# Z80-Clock-And-Reset-1-2.net
KiCad netlist of a schematic drawn in EAGLE
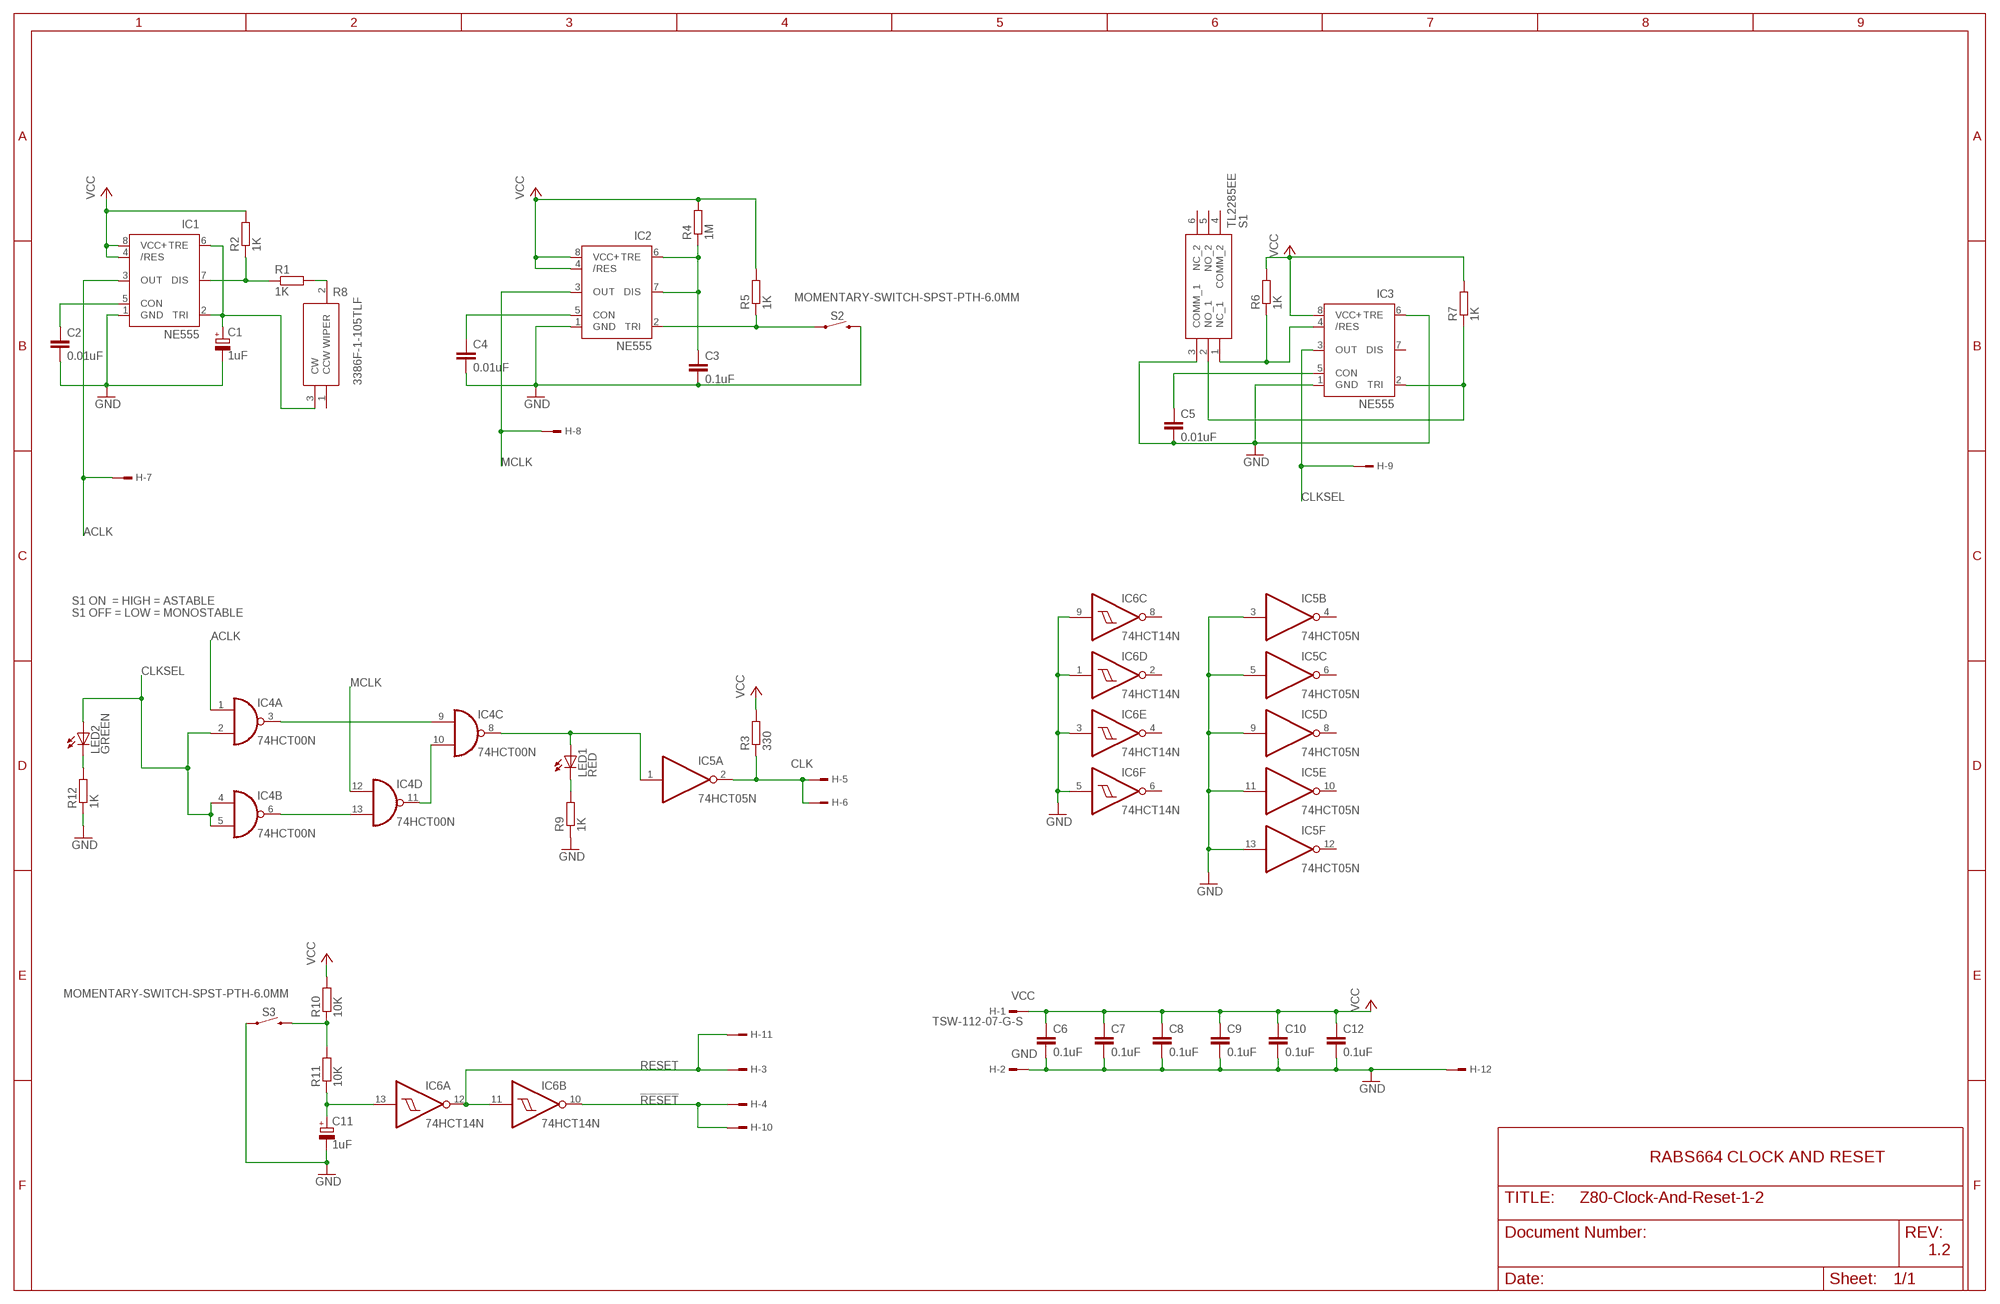
[diagram p0: schematic, sheet 1]

(export (version "E")
  (design (tool "Eeschema 10.0.6"))
  (components
    (comp (ref "C1")
      (value "1uF")
      (footprint "eagle-import:E2,5-6E")
      (libsource (lib "eagle-import") (part "CPOL-EUE2,5-6E"))
    )
    (comp (ref "C2")
      (value "0.01uF")
      (footprint "eagle-import:C050-025X075")
      (libsource (lib "eagle-import") (part "C-EU050-025X075"))
    )
    (comp (ref "C3")
      (value "0.1uF")
      (footprint "eagle-import:C050-025X075")
      (libsource (lib "eagle-import") (part "C-EU050-025X075"))
    )
    (comp (ref "C4")
      (value "0.01uF")
      (footprint "eagle-import:C050-025X075")
      (libsource (lib "eagle-import") (part "C-EU050-025X075"))
    )
    (comp (ref "C5")
      (value "0.01uF")
      (footprint "eagle-import:C050-025X075")
      (libsource (lib "eagle-import") (part "C-EU050-025X075"))
    )
    (comp (ref "C6")
      (value "0.1uF")
      (footprint "eagle-import:C050-025X075")
      (libsource (lib "eagle-import") (part "C-EU050-025X075"))
    )
    (comp (ref "C7")
      (value "0.1uF")
      (footprint "eagle-import:C050-025X075")
      (libsource (lib "eagle-import") (part "C-EU050-025X075"))
    )
    (comp (ref "C8")
      (value "0.1uF")
      (footprint "eagle-import:C050-025X075")
      (libsource (lib "eagle-import") (part "C-EU050-025X075"))
    )
    (comp (ref "C9")
      (value "0.1uF")
      (footprint "eagle-import:C050-025X075")
      (libsource (lib "eagle-import") (part "C-EU050-025X075"))
    )
    (comp (ref "C10")
      (value "0.1uF")
      (footprint "eagle-import:C050-025X075")
      (libsource (lib "eagle-import") (part "C-EU050-025X075"))
    )
    (comp (ref "C11")
      (value "1uF")
      (footprint "eagle-import:E2,5-6E")
      (libsource (lib "eagle-import") (part "CPOL-EUE2,5-6E"))
    )
    (comp (ref "C12")
      (value "0.1uF")
      (footprint "eagle-import:C050-025X075")
      (libsource (lib "eagle-import") (part "C-EU050-025X075"))
    )
    (comp (ref "H")
      (value "TSW-112-07-G-S")
      (footprint "eagle-import:TSW-112-XX-G-S")
      (fields (field (name "MF") "Samtec Inc."))
      (libsource (lib "eagle-import") (part "TSW-112--G-S07"))
    )
    (comp (ref "IC1")
      (value "NE555")
      (footprint "eagle-import:DIL-08")
      (fields (field (name "MF") "Arrow Electronics") (field (name "MPN") "NE555N"))
      (libsource (lib "eagle-import") (part "NE555"))
    )
    (comp (ref "IC2")
      (value "NE555")
      (footprint "eagle-import:DIL-08")
      (fields (field (name "MF") "Arrow Electronics") (field (name "MPN") "NE555N"))
      (libsource (lib "eagle-import") (part "NE555"))
    )
    (comp (ref "IC3")
      (value "NE555")
      (footprint "eagle-import:DIL-08")
      (fields (field (name "MF") "Arrow Electronics") (field (name "MPN") "NE555N"))
      (libsource (lib "eagle-import") (part "NE555"))
    )
    (comp (ref "IC4")
      (value "74HCT00N")
      (footprint "eagle-import:DIL14")
      (libsource (lib "eagle-import") (part "7400NHCT"))
    )
    (comp (ref "IC5")
      (value "74HCT05N")
      (footprint "eagle-import:DIL14")
      (libsource (lib "eagle-import") (part "7405NHCT"))
    )
    (comp (ref "IC6")
      (value "74HCT14N")
      (footprint "eagle-import:DIL14")
      (libsource (lib "eagle-import") (part "7414NHCT"))
    )
    (comp (ref "LED1")
      (value "RED")
      (footprint "eagle-import:LED3MM")
      (libsource (lib "eagle-import") (part "LED3MM"))
    )
    (comp (ref "LED2")
      (value "GREEN")
      (footprint "eagle-import:LED3MM")
      (libsource (lib "eagle-import") (part "LED3MM"))
    )
    (comp (ref "R1")
      (value "1K")
      (footprint "eagle-import:0207_10")
      (libsource (lib "eagle-import") (part "R-EU_0207/10"))
    )
    (comp (ref "R2")
      (value "1K")
      (footprint "eagle-import:0207_10")
      (libsource (lib "eagle-import") (part "R-EU_0207/10"))
    )
    (comp (ref "R3")
      (value "330")
      (footprint "eagle-import:0207_10")
      (libsource (lib "eagle-import") (part "R-EU_0207/10"))
    )
    (comp (ref "R4")
      (value "1M")
      (footprint "eagle-import:0207_10")
      (libsource (lib "eagle-import") (part "R-EU_0207/10"))
    )
    (comp (ref "R5")
      (value "1K")
      (footprint "eagle-import:0207_10")
      (libsource (lib "eagle-import") (part "R-EU_0207/10"))
    )
    (comp (ref "R6")
      (value "1K")
      (footprint "eagle-import:0207_10")
      (libsource (lib "eagle-import") (part "R-EU_0207/10"))
    )
    (comp (ref "R7")
      (value "1K")
      (footprint "eagle-import:0207_10")
      (libsource (lib "eagle-import") (part "R-EU_0207/10"))
    )
    (comp (ref "R8")
      (value "3386F-1-103TLF")
      (footprint "eagle-import:3386F1103TLF")
      (fields (field (name "MOUSER_PART_NUMBER") "652-3386F-1-103TLF"))
      (libsource (lib "eagle-import") (part "3386F-1-103TLF"))
    )
    (comp (ref "R9")
      (value "1K")
      (footprint "eagle-import:0207_10")
      (libsource (lib "eagle-import") (part "R-EU_0207/10"))
    )
    (comp (ref "R10")
      (value "10K")
      (footprint "eagle-import:0207_10")
      (libsource (lib "eagle-import") (part "R-EU_0207/10"))
    )
    (comp (ref "R11")
      (value "10K")
      (footprint "eagle-import:0207_10")
      (libsource (lib "eagle-import") (part "R-EU_0207/10"))
    )
    (comp (ref "R12")
      (value "1K")
      (footprint "eagle-import:0207_10")
      (libsource (lib "eagle-import") (part "R-EU_0207/10"))
    )
    (comp (ref "S1")
      (value "TL2285EE")
      (footprint "eagle-import:TL2285EE")
      (fields (field (name "MOUSER_PART_NUMBER") "612-TL2285EE"))
      (libsource (lib "eagle-import") (part "TL2285EE"))
    )
    (comp (ref "S2")
      (value "MOMENTARY-SWITCH-SPST-PTH-6.0MM")
      (footprint "eagle-import:TACTILE_SWITCH_PTH_6.0MM")
      (libsource (lib "eagle-import") (part "MOMENTARY-SWITCH-SPST-PTH-6.0MM"))
    )
    (comp (ref "S3")
      (value "MOMENTARY-SWITCH-SPST-PTH-6.0MM")
      (footprint "eagle-import:TACTILE_SWITCH_PTH_6.0MM")
      (libsource (lib "eagle-import") (part "MOMENTARY-SWITCH-SPST-PTH-6.0MM"))
    )
  )
  (nets
    (net (code "1") (name "/ACLK") (class "Default")
      (node (ref "H") (pin "7") (pinfunction "1_7") (pintype "passive"))
      (node (ref "IC1") (pin "3") (pinfunction "OUT_3") (pintype "output"))
      (node (ref "IC4") (pin "1") (pinfunction "I0_1") (pintype "input"))
    )
    (net (code "2") (name "/CLK") (class "Default")
      (node (ref "H") (pin "5") (pinfunction "1_5") (pintype "passive"))
      (node (ref "H") (pin "6") (pinfunction "1_6") (pintype "passive"))
      (node (ref "IC5") (pin "2") (pinfunction "O_2") (pintype "open_collector"))
      (node (ref "R3") (pin "1") (pinfunction "1_1") (pintype "passive"))
    )
    (net (code "3") (name "/CLKSEL") (class "Default")
      (node (ref "H") (pin "9") (pinfunction "1_9") (pintype "passive"))
      (node (ref "IC3") (pin "3") (pinfunction "OUT_3") (pintype "output"))
      (node (ref "IC4") (pin "2") (pinfunction "I1_2") (pintype "input"))
      (node (ref "IC4") (pin "4") (pinfunction "I0_4") (pintype "input"))
      (node (ref "IC4") (pin "5") (pinfunction "I1_5") (pintype "input"))
      (node (ref "LED2") (pin "A") (pinfunction "A_A") (pintype "passive"))
    )
    (net (code "4") (name "/MCLK") (class "Default")
      (node (ref "H") (pin "8") (pinfunction "1_8") (pintype "passive"))
      (node (ref "IC2") (pin "3") (pinfunction "OUT_3") (pintype "output"))
      (node (ref "IC4") (pin "12") (pinfunction "I0_12") (pintype "input"))
    )
    (net (code "5") (name "/RESET") (class "Default")
      (node (ref "H") (pin "11") (pinfunction "1_11") (pintype "passive"))
      (node (ref "H") (pin "3") (pinfunction "1_3") (pintype "passive"))
      (node (ref "IC6") (pin "11") (pinfunction "I_11") (pintype "input"))
      (node (ref "IC6") (pin "12") (pinfunction "O_12") (pintype "output"))
    )
    (net (code "6") (name "/~{RESET}") (class "Default")
      (node (ref "H") (pin "10") (pinfunction "1_10") (pintype "passive"))
      (node (ref "H") (pin "4") (pinfunction "1_4") (pintype "passive"))
      (node (ref "IC6") (pin "10") (pinfunction "O_10") (pintype "output"))
    )
    (net (code "7") (name "GND") (class "Default")
      (node (ref "C1") (pin "-") (pinfunction "-_-") (pintype "passive"))
      (node (ref "C10") (pin "2") (pinfunction "2_2") (pintype "passive"))
      (node (ref "C11") (pin "-") (pinfunction "-_-") (pintype "passive"))
      (node (ref "C12") (pin "2") (pinfunction "2_2") (pintype "passive"))
      (node (ref "C2") (pin "2") (pinfunction "2_2") (pintype "passive"))
      (node (ref "C3") (pin "2") (pinfunction "2_2") (pintype "passive"))
      (node (ref "C4") (pin "2") (pinfunction "2_2") (pintype "passive"))
      (node (ref "C5") (pin "2") (pinfunction "2_2") (pintype "passive"))
      (node (ref "C6") (pin "2") (pinfunction "2_2") (pintype "passive"))
      (node (ref "C7") (pin "2") (pinfunction "2_2") (pintype "passive"))
      (node (ref "C8") (pin "2") (pinfunction "2_2") (pintype "passive"))
      (node (ref "C9") (pin "2") (pinfunction "2_2") (pintype "passive"))
      (node (ref "H") (pin "12") (pinfunction "1_12") (pintype "passive"))
      (node (ref "H") (pin "2") (pinfunction "1_2") (pintype "passive"))
      (node (ref "IC1") (pin "1") (pinfunction "GND_1") (pintype "power_in"))
      (node (ref "IC2") (pin "1") (pinfunction "GND_1") (pintype "power_in"))
      (node (ref "IC3") (pin "1") (pinfunction "GND_1") (pintype "power_in"))
      (node (ref "IC3") (pin "6") (pinfunction "TRE_6") (pintype "input"))
      (node (ref "IC5") (pin "11") (pinfunction "I_11") (pintype "input"))
      (node (ref "IC5") (pin "13") (pinfunction "I_13") (pintype "input"))
      (node (ref "IC5") (pin "3") (pinfunction "I_3") (pintype "input"))
      (node (ref "IC5") (pin "5") (pinfunction "I_5") (pintype "input"))
      (node (ref "IC5") (pin "9") (pinfunction "I_9") (pintype "input"))
      (node (ref "IC6") (pin "1") (pinfunction "I_1") (pintype "input"))
      (node (ref "IC6") (pin "3") (pinfunction "I_3") (pintype "input"))
      (node (ref "IC6") (pin "5") (pinfunction "I_5") (pintype "input"))
      (node (ref "IC6") (pin "9") (pinfunction "I_9") (pintype "input"))
      (node (ref "R12") (pin "1") (pinfunction "1_1") (pintype "passive"))
      (node (ref "R9") (pin "1") (pinfunction "1_1") (pintype "passive"))
      (node (ref "S1") (pin "3") (pinfunction "COMM_1_3") (pintype "bidirectional"))
      (node (ref "S2") (pin "3") (pinfunction "2_3") (pintype "passive"))
      (node (ref "S3") (pin "1") (pinfunction "1_1") (pintype "passive"))
    )
    (net (code "8") (name "Net-(IC1-CON)") (class "Default")
      (node (ref "C2") (pin "1") (pinfunction "1_1") (pintype "passive"))
      (node (ref "IC1") (pin "5") (pinfunction "CON_5") (pintype "input"))
    )
    (net (code "9") (name "Net-(IC1-DIS)") (class "Default")
      (node (ref "IC1") (pin "7") (pinfunction "DIS_7") (pintype "input"))
      (node (ref "R1") (pin "1") (pinfunction "1_1") (pintype "passive"))
      (node (ref "R2") (pin "1") (pinfunction "1_1") (pintype "passive"))
    )
    (net (code "10") (name "Net-(IC1-TRE)") (class "Default")
      (node (ref "C1") (pin "+") (pinfunction "+_+") (pintype "passive"))
      (node (ref "IC1") (pin "2") (pinfunction "TRI_2") (pintype "input"))
      (node (ref "IC1") (pin "6") (pinfunction "TRE_6") (pintype "input"))
      (node (ref "R8") (pin "3") (pinfunction "CW_3") (pintype "bidirectional"))
    )
    (net (code "11") (name "Net-(IC2-CON)") (class "Default")
      (node (ref "C4") (pin "1") (pinfunction "1_1") (pintype "passive"))
      (node (ref "IC2") (pin "5") (pinfunction "CON_5") (pintype "input"))
    )
    (net (code "12") (name "Net-(IC2-DIS)") (class "Default")
      (node (ref "C3") (pin "1") (pinfunction "1_1") (pintype "passive"))
      (node (ref "IC2") (pin "6") (pinfunction "TRE_6") (pintype "input"))
      (node (ref "IC2") (pin "7") (pinfunction "DIS_7") (pintype "input"))
      (node (ref "R4") (pin "1") (pinfunction "1_1") (pintype "passive"))
    )
    (net (code "13") (name "Net-(IC2-TRI)") (class "Default")
      (node (ref "IC2") (pin "2") (pinfunction "TRI_2") (pintype "input"))
      (node (ref "R5") (pin "1") (pinfunction "1_1") (pintype "passive"))
      (node (ref "S2") (pin "1") (pinfunction "1_1") (pintype "passive"))
    )
    (net (code "14") (name "Net-(IC3-CON)") (class "Default")
      (node (ref "C5") (pin "1") (pinfunction "1_1") (pintype "passive"))
      (node (ref "IC3") (pin "5") (pinfunction "CON_5") (pintype "input"))
    )
    (net (code "15") (name "Net-(IC3-TRI)") (class "Default")
      (node (ref "IC3") (pin "2") (pinfunction "TRI_2") (pintype "input"))
      (node (ref "R7") (pin "1") (pinfunction "1_1") (pintype "passive"))
      (node (ref "S1") (pin "2") (pinfunction "NO_1_2") (pintype "bidirectional"))
    )
    (net (code "16") (name "Net-(IC3-{slash}RES)") (class "Default")
      (node (ref "IC3") (pin "4") (pinfunction "/RES_4") (pintype "input"))
      (node (ref "R6") (pin "1") (pinfunction "1_1") (pintype "passive"))
      (node (ref "S1") (pin "1") (pinfunction "NC_1_1") (pintype "bidirectional"))
    )
    (net (code "17") (name "Net-(IC4A-O)") (class "Default")
      (node (ref "IC4") (pin "3") (pinfunction "O_3") (pintype "output"))
      (node (ref "IC4") (pin "9") (pinfunction "I0_9") (pintype "input"))
    )
    (net (code "18") (name "Net-(IC4B-O)") (class "Default")
      (node (ref "IC4") (pin "13") (pinfunction "I1_13") (pintype "input"))
      (node (ref "IC4") (pin "6") (pinfunction "O_6") (pintype "output"))
    )
    (net (code "19") (name "Net-(IC4C-I1)") (class "Default")
      (node (ref "IC4") (pin "10") (pinfunction "I1_10") (pintype "input"))
      (node (ref "IC4") (pin "11") (pinfunction "O_11") (pintype "output"))
    )
    (net (code "20") (name "Net-(IC4C-O)") (class "Default")
      (node (ref "IC4") (pin "8") (pinfunction "O_8") (pintype "output"))
      (node (ref "IC5") (pin "1") (pinfunction "I_1") (pintype "input"))
      (node (ref "LED1") (pin "A") (pinfunction "A_A") (pintype "passive"))
    )
    (net (code "21") (name "Net-(IC6A-I)") (class "Default")
      (node (ref "C11") (pin "+") (pinfunction "+_+") (pintype "passive"))
      (node (ref "IC6") (pin "13") (pinfunction "I_13") (pintype "input"))
      (node (ref "R11") (pin "1") (pinfunction "1_1") (pintype "passive"))
    )
    (net (code "22") (name "Net-(LED1-C)") (class "Default")
      (node (ref "LED1") (pin "K") (pinfunction "C_K") (pintype "passive"))
      (node (ref "R9") (pin "2") (pinfunction "2_2") (pintype "passive"))
    )
    (net (code "23") (name "Net-(LED2-C)") (class "Default")
      (node (ref "LED2") (pin "K") (pinfunction "C_K") (pintype "passive"))
      (node (ref "R12") (pin "2") (pinfunction "2_2") (pintype "passive"))
    )
    (net (code "24") (name "Net-(R8-WIPER)") (class "Default")
      (node (ref "R1") (pin "2") (pinfunction "2_2") (pintype "passive"))
      (node (ref "R8") (pin "2") (pinfunction "WIPER_2") (pintype "bidirectional"))
    )
    (net (code "25") (name "Net-(S3-2)") (class "Default")
      (node (ref "R10") (pin "1") (pinfunction "1_1") (pintype "passive"))
      (node (ref "R11") (pin "2") (pinfunction "2_2") (pintype "passive"))
      (node (ref "S3") (pin "3") (pinfunction "2_3") (pintype "passive"))
    )
    (net (code "26") (name "VCC") (class "Default")
      (node (ref "C10") (pin "1") (pinfunction "1_1") (pintype "passive"))
      (node (ref "C12") (pin "1") (pinfunction "1_1") (pintype "passive"))
      (node (ref "C6") (pin "1") (pinfunction "1_1") (pintype "passive"))
      (node (ref "C7") (pin "1") (pinfunction "1_1") (pintype "passive"))
      (node (ref "C8") (pin "1") (pinfunction "1_1") (pintype "passive"))
      (node (ref "C9") (pin "1") (pinfunction "1_1") (pintype "passive"))
      (node (ref "H") (pin "1") (pinfunction "1_1") (pintype "passive"))
      (node (ref "IC1") (pin "4") (pinfunction "/RES_4") (pintype "input"))
      (node (ref "IC1") (pin "8") (pinfunction "VCC+_8") (pintype "power_in"))
      (node (ref "IC2") (pin "4") (pinfunction "/RES_4") (pintype "input"))
      (node (ref "IC2") (pin "8") (pinfunction "VCC+_8") (pintype "power_in"))
      (node (ref "IC3") (pin "8") (pinfunction "VCC+_8") (pintype "power_in"))
      (node (ref "R10") (pin "2") (pinfunction "2_2") (pintype "passive"))
      (node (ref "R2") (pin "2") (pinfunction "2_2") (pintype "passive"))
      (node (ref "R3") (pin "2") (pinfunction "2_2") (pintype "passive"))
      (node (ref "R4") (pin "2") (pinfunction "2_2") (pintype "passive"))
      (node (ref "R5") (pin "2") (pinfunction "2_2") (pintype "passive"))
      (node (ref "R6") (pin "2") (pinfunction "2_2") (pintype "passive"))
      (node (ref "R7") (pin "2") (pinfunction "2_2") (pintype "passive"))
    )
    (net (code "27") (name "unconnected-(IC3-DIS-Pad7)") (class "Default")
      (node (ref "IC3") (pin "7") (pinfunction "DIS_7") (pintype "input"))
    )
    (net (code "28") (name "unconnected-(IC5B-O-Pad4)") (class "Default")
      (node (ref "IC5") (pin "4") (pinfunction "O_4") (pintype "open_collector"))
    )
    (net (code "29") (name "unconnected-(IC5C-O-Pad6)") (class "Default")
      (node (ref "IC5") (pin "6") (pinfunction "O_6") (pintype "open_collector"))
    )
    (net (code "30") (name "unconnected-(IC5D-O-Pad8)") (class "Default")
      (node (ref "IC5") (pin "8") (pinfunction "O_8") (pintype "open_collector"))
    )
    (net (code "31") (name "unconnected-(IC5E-O-Pad10)") (class "Default")
      (node (ref "IC5") (pin "10") (pinfunction "O_10") (pintype "open_collector"))
    )
    (net (code "32") (name "unconnected-(IC5F-O-Pad12)") (class "Default")
      (node (ref "IC5") (pin "12") (pinfunction "O_12") (pintype "open_collector"))
    )
    (net (code "33") (name "unconnected-(IC6C-O-Pad8)") (class "Default")
      (node (ref "IC6") (pin "8") (pinfunction "O_8") (pintype "output"))
    )
    (net (code "34") (name "unconnected-(IC6D-O-Pad2)") (class "Default")
      (node (ref "IC6") (pin "2") (pinfunction "O_2") (pintype "output"))
    )
    (net (code "35") (name "unconnected-(IC6E-O-Pad4)") (class "Default")
      (node (ref "IC6") (pin "4") (pinfunction "O_4") (pintype "output"))
    )
    (net (code "36") (name "unconnected-(IC6F-O-Pad6)") (class "Default")
      (node (ref "IC6") (pin "6") (pinfunction "O_6") (pintype "output"))
    )
    (net (code "37") (name "unconnected-(R8-CCW-Pad1)") (class "Default")
      (node (ref "R8") (pin "1") (pinfunction "CCW_1") (pintype "bidirectional"))
    )
    (net (code "38") (name "unconnected-(S1-COMM_2-Pad4)") (class "Default")
      (node (ref "S1") (pin "4") (pinfunction "COMM_2_4") (pintype "bidirectional"))
    )
    (net (code "39") (name "unconnected-(S1-NC_2-Pad6)") (class "Default")
      (node (ref "S1") (pin "6") (pinfunction "NC_2_6") (pintype "bidirectional"))
    )
    (net (code "40") (name "unconnected-(S1-NO_2-Pad5)") (class "Default")
      (node (ref "S1") (pin "5") (pinfunction "NO_2_5") (pintype "bidirectional"))
    )
  )
)
